# captouchIC.net
KiCad netlist of a schematic drawn in EAGLE
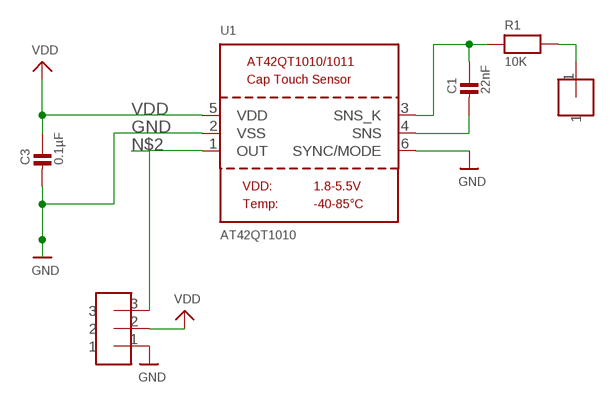
[diagram p0: schematic, sheet 1]

(export (version "E")
  (design (tool "Eeschema 10.0.6"))
  (components
    (comp (ref "C1")
      (value "22nF")
      (footprint "eagle-import:_0805")
      (libsource (lib "eagle-import") (part "CAP_CERAMIC_0805"))
    )
    (comp (ref "C3")
      (value "0.1µF")
      (footprint "eagle-import:_0805")
      (libsource (lib "eagle-import") (part "CAP_CERAMIC_0805"))
    )
    (comp (ref "R1")
      (value "10K")
      (footprint "eagle-import:_0805")
      (libsource (lib "eagle-import") (part "RESISTOR_0805"))
    )
    (comp (ref "U$1")
      (value "HEADER-1-TESTPOINT")
      (footprint "eagle-import:TESTPOINT-1")
      (libsource (lib "eagle-import") (part "HEADER-1-TESTPOINT"))
    )
    (comp (ref "U$6")
      (value "HEADER-3")
      (footprint "eagle-import:HEADER-3")
      (libsource (lib "eagle-import") (part "HEADER-3"))
    )
    (comp (ref "U1")
      (value "AT42QT1010")
      (footprint "eagle-import:SOT23-6")
      (libsource (lib "eagle-import") (part "AT42QT1010/1"))
    )
  )
  (nets
    (net (code "1") (name "/N$2") (class "Default")
      (node (ref "U$6") (pin "3") (pinfunction "3_3") (pintype "bidirectional"))
      (node (ref "U1") (pin "1") (pinfunction "OUT_1") (pintype "output"))
    )
    (net (code "2") (name "GND") (class "Default")
      (node (ref "C3") (pin "2") (pinfunction "P$2_2") (pintype "passive"))
      (node (ref "U$6") (pin "1") (pinfunction "1_1") (pintype "bidirectional"))
      (node (ref "U1") (pin "2") (pinfunction "VSS_2") (pintype "power_in"))
      (node (ref "U1") (pin "6") (pinfunction "SYNC/MODE_6") (pintype "input"))
    )
    (net (code "3") (name "Net-(C1-P$1)") (class "Default")
      (node (ref "C1") (pin "1") (pinfunction "P$1_1") (pintype "passive"))
      (node (ref "R1") (pin "1") (pinfunction "1_1") (pintype "passive"))
      (node (ref "U1") (pin "3") (pinfunction "SNS_K_3") (pintype "bidirectional"))
    )
    (net (code "4") (name "Net-(C1-P$2)") (class "Default")
      (node (ref "C1") (pin "2") (pinfunction "P$2_2") (pintype "passive"))
      (node (ref "U1") (pin "4") (pinfunction "SNS_4") (pintype "bidirectional"))
    )
    (net (code "5") (name "Net-(R1-Pad2)") (class "Default")
      (node (ref "R1") (pin "2") (pinfunction "2_2") (pintype "passive"))
      (node (ref "U$1") (pin "1") (pinfunction "1_1") (pintype "bidirectional"))
    )
    (net (code "6") (name "VDD") (class "Default")
      (node (ref "C3") (pin "1") (pinfunction "P$1_1") (pintype "passive"))
      (node (ref "U$6") (pin "2") (pinfunction "2_2") (pintype "bidirectional"))
      (node (ref "U1") (pin "5") (pinfunction "VDD_5") (pintype "power_in"))
    )
  )
)
